# v0_7.net
KiCad netlist of a schematic drawn in EAGLE
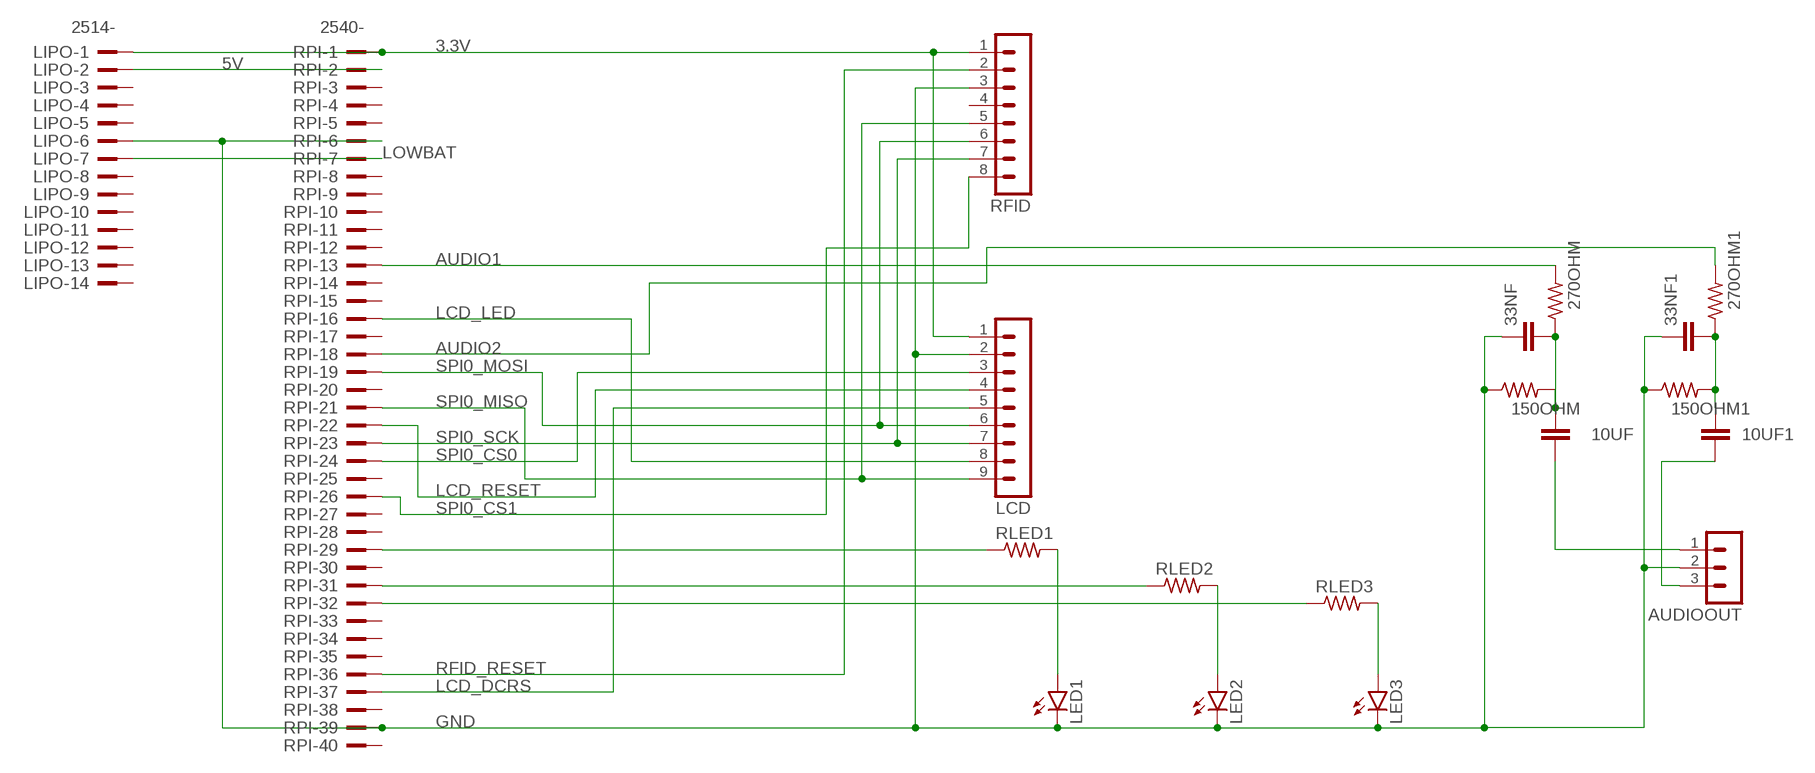
[diagram p0: schematic, sheet 1]

(export (version "E")
  (design (tool "Eeschema 10.0.6"))
  (components
    (comp (ref "10UF")
      (value "C-EU025-025X050")
      (footprint "eagle-import:C025-025X050")
      (libsource (lib "eagle-import") (part "C-EU025-025X050"))
    )
    (comp (ref "10UF1")
      (value "C-EU025-025X050")
      (footprint "eagle-import:C025-025X050")
      (libsource (lib "eagle-import") (part "C-EU025-025X050"))
    )
    (comp (ref "33NF")
      (value "C-EU025-025X050")
      (footprint "eagle-import:C025-025X050")
      (libsource (lib "eagle-import") (part "C-EU025-025X050"))
    )
    (comp (ref "33NF1")
      (value "C-EU025-025X050")
      (footprint "eagle-import:C025-025X050")
      (libsource (lib "eagle-import") (part "C-EU025-025X050"))
    )
    (comp (ref "150OHM")
      (value "R-US_0204/5")
      (footprint "eagle-import:0204_5")
      (libsource (lib "eagle-import") (part "R-US_0204/5"))
    )
    (comp (ref "150OHM1")
      (value "R-US_0204/5")
      (footprint "eagle-import:0204_5")
      (libsource (lib "eagle-import") (part "R-US_0204/5"))
    )
    (comp (ref "270OHM")
      (value "R-US_0204/5")
      (footprint "eagle-import:0204_5")
      (libsource (lib "eagle-import") (part "R-US_0204/5"))
    )
    (comp (ref "270OHM1")
      (value "R-US_0204/5")
      (footprint "eagle-import:0204_5")
      (libsource (lib "eagle-import") (part "R-US_0204/5"))
    )
    (comp (ref "AUDIOOUT")
      (value "MA03-1")
      (footprint "eagle-import:MA03-1")
      (libsource (lib "eagle-import") (part "MA03-1"))
    )
    (comp (ref "LCD")
      (value "MA09-1")
      (footprint "eagle-import:MA09-1")
      (libsource (lib "eagle-import") (part "MA09-1"))
    )
    (comp (ref "LED1")
      (value "LED3MM")
      (footprint "eagle-import:LED3MM")
      (libsource (lib "eagle-import") (part "LED3MM"))
    )
    (comp (ref "LED2")
      (value "LED3MM")
      (footprint "eagle-import:LED3MM")
      (libsource (lib "eagle-import") (part "LED3MM"))
    )
    (comp (ref "LED3")
      (value "LED3MM")
      (footprint "eagle-import:LED3MM")
      (libsource (lib "eagle-import") (part "LED3MM"))
    )
    (comp (ref "LIPO")
      (value "2514-")
      (footprint "eagle-import:PAK100_2500-14")
      (libsource (lib "eagle-import") (part "2514-"))
    )
    (comp (ref "RFID")
      (value "MA08-1")
      (footprint "eagle-import:MA08-1")
      (libsource (lib "eagle-import") (part "MA08-1"))
    )
    (comp (ref "RLED1")
      (value "R-US_0204/5")
      (footprint "eagle-import:0204_5")
      (libsource (lib "eagle-import") (part "R-US_0204/5"))
    )
    (comp (ref "RLED2")
      (value "R-US_0204/5")
      (footprint "eagle-import:0204_5")
      (libsource (lib "eagle-import") (part "R-US_0204/5"))
    )
    (comp (ref "RLED3")
      (value "R-US_0204/5")
      (footprint "eagle-import:0204_5")
      (libsource (lib "eagle-import") (part "R-US_0204/5"))
    )
    (comp (ref "RPI")
      (value "2540-")
      (footprint "eagle-import:PAK100_2500-40")
      (libsource (lib "eagle-import") (part "2540-"))
    )
  )
  (nets
    (net (code "1") (name "/3.3V") (class "Default")
      (node (ref "LCD") (pin "1") (pinfunction "1_1") (pintype "passive"))
      (node (ref "LIPO") (pin "1") (pinfunction "KL_1") (pintype "passive"))
      (node (ref "RFID") (pin "1") (pinfunction "1_1") (pintype "passive"))
      (node (ref "RPI") (pin "1") (pinfunction "KL_1") (pintype "passive"))
    )
    (net (code "2") (name "/5V") (class "Default")
      (node (ref "LIPO") (pin "2") (pinfunction "KL_2") (pintype "passive"))
      (node (ref "RPI") (pin "2") (pinfunction "KL_2") (pintype "passive"))
    )
    (net (code "3") (name "/AUDIO1") (class "Default")
      (node (ref "270OHM") (pin "2") (pinfunction "2_2") (pintype "passive"))
      (node (ref "RPI") (pin "13") (pinfunction "KL_13") (pintype "passive"))
    )
    (net (code "4") (name "/AUDIO2") (class "Default")
      (node (ref "270OHM1") (pin "2") (pinfunction "2_2") (pintype "passive"))
      (node (ref "RPI") (pin "18") (pinfunction "KL_18") (pintype "passive"))
    )
    (net (code "5") (name "/GND") (class "Default")
      (node (ref "150OHM") (pin "1") (pinfunction "1_1") (pintype "passive"))
      (node (ref "150OHM1") (pin "1") (pinfunction "1_1") (pintype "passive"))
      (node (ref "33NF") (pin "1") (pinfunction "1_1") (pintype "passive"))
      (node (ref "33NF1") (pin "1") (pinfunction "1_1") (pintype "passive"))
      (node (ref "AUDIOOUT") (pin "2") (pinfunction "2_2") (pintype "passive"))
      (node (ref "LCD") (pin "2") (pinfunction "2_2") (pintype "passive"))
      (node (ref "LED1") (pin "K") (pinfunction "C_K") (pintype "passive"))
      (node (ref "LED2") (pin "K") (pinfunction "C_K") (pintype "passive"))
      (node (ref "LED3") (pin "K") (pinfunction "C_K") (pintype "passive"))
      (node (ref "LIPO") (pin "6") (pinfunction "KL_6") (pintype "passive"))
      (node (ref "RFID") (pin "3") (pinfunction "3_3") (pintype "passive"))
      (node (ref "RPI") (pin "39") (pinfunction "KL_39") (pintype "passive"))
      (node (ref "RPI") (pin "6") (pinfunction "KL_6") (pintype "passive"))
    )
    (net (code "6") (name "/LCD_DCRS") (class "Default")
      (node (ref "LCD") (pin "5") (pinfunction "5_5") (pintype "passive"))
      (node (ref "RPI") (pin "37") (pinfunction "KL_37") (pintype "passive"))
    )
    (net (code "7") (name "/LCD_LED") (class "Default")
      (node (ref "LCD") (pin "8") (pinfunction "8_8") (pintype "passive"))
      (node (ref "RPI") (pin "16") (pinfunction "KL_16") (pintype "passive"))
    )
    (net (code "8") (name "/LCD_RESET") (class "Default")
      (node (ref "LCD") (pin "4") (pinfunction "4_4") (pintype "passive"))
      (node (ref "RPI") (pin "22") (pinfunction "KL_22") (pintype "passive"))
    )
    (net (code "9") (name "/LOWBAT") (class "Default")
      (node (ref "LIPO") (pin "7") (pinfunction "KL_7") (pintype "passive"))
      (node (ref "RPI") (pin "7") (pinfunction "KL_7") (pintype "passive"))
    )
    (net (code "10") (name "/RFID_RESET") (class "Default")
      (node (ref "RFID") (pin "2") (pinfunction "2_2") (pintype "passive"))
      (node (ref "RPI") (pin "36") (pinfunction "KL_36") (pintype "passive"))
    )
    (net (code "11") (name "/SPI0_CS0") (class "Default")
      (node (ref "LCD") (pin "3") (pinfunction "3_3") (pintype "passive"))
      (node (ref "RPI") (pin "24") (pinfunction "KL_24") (pintype "passive"))
    )
    (net (code "12") (name "/SPI0_CS1") (class "Default")
      (node (ref "RFID") (pin "8") (pinfunction "8_8") (pintype "passive"))
      (node (ref "RPI") (pin "26") (pinfunction "KL_26") (pintype "passive"))
    )
    (net (code "13") (name "/SPI0_MISO") (class "Default")
      (node (ref "LCD") (pin "9") (pinfunction "9_9") (pintype "passive"))
      (node (ref "RFID") (pin "5") (pinfunction "5_5") (pintype "passive"))
      (node (ref "RPI") (pin "21") (pinfunction "KL_21") (pintype "passive"))
    )
    (net (code "14") (name "/SPI0_MOSI") (class "Default")
      (node (ref "LCD") (pin "6") (pinfunction "6_6") (pintype "passive"))
      (node (ref "RFID") (pin "6") (pinfunction "6_6") (pintype "passive"))
      (node (ref "RPI") (pin "19") (pinfunction "KL_19") (pintype "passive"))
    )
    (net (code "15") (name "/SPI0_SCK") (class "Default")
      (node (ref "LCD") (pin "7") (pinfunction "7_7") (pintype "passive"))
      (node (ref "RFID") (pin "7") (pinfunction "7_7") (pintype "passive"))
      (node (ref "RPI") (pin "23") (pinfunction "KL_23") (pintype "passive"))
    )
    (net (code "16") (name "Net-(10UF-Pad1)") (class "Default")
      (node (ref "10UF") (pin "1") (pinfunction "1_1") (pintype "passive"))
      (node (ref "AUDIOOUT") (pin "1") (pinfunction "1_1") (pintype "passive"))
    )
    (net (code "17") (name "Net-(10UF-Pad2)") (class "Default")
      (node (ref "10UF") (pin "2") (pinfunction "2_2") (pintype "passive"))
      (node (ref "150OHM") (pin "2") (pinfunction "2_2") (pintype "passive"))
      (node (ref "270OHM") (pin "1") (pinfunction "1_1") (pintype "passive"))
      (node (ref "33NF") (pin "2") (pinfunction "2_2") (pintype "passive"))
    )
    (net (code "18") (name "Net-(10UF1-Pad1)") (class "Default")
      (node (ref "10UF1") (pin "1") (pinfunction "1_1") (pintype "passive"))
      (node (ref "AUDIOOUT") (pin "3") (pinfunction "3_3") (pintype "passive"))
    )
    (net (code "19") (name "Net-(10UF1-Pad2)") (class "Default")
      (node (ref "10UF1") (pin "2") (pinfunction "2_2") (pintype "passive"))
      (node (ref "150OHM1") (pin "2") (pinfunction "2_2") (pintype "passive"))
      (node (ref "270OHM1") (pin "1") (pinfunction "1_1") (pintype "passive"))
      (node (ref "33NF1") (pin "2") (pinfunction "2_2") (pintype "passive"))
    )
    (net (code "20") (name "Net-(LED1-PadA)") (class "Default")
      (node (ref "LED1") (pin "A") (pinfunction "A_A") (pintype "passive"))
      (node (ref "RLED1") (pin "2") (pinfunction "2_2") (pintype "passive"))
    )
    (net (code "21") (name "Net-(LED2-PadA)") (class "Default")
      (node (ref "LED2") (pin "A") (pinfunction "A_A") (pintype "passive"))
      (node (ref "RLED2") (pin "2") (pinfunction "2_2") (pintype "passive"))
    )
    (net (code "22") (name "Net-(LED3-PadA)") (class "Default")
      (node (ref "LED3") (pin "A") (pinfunction "A_A") (pintype "passive"))
      (node (ref "RLED3") (pin "2") (pinfunction "2_2") (pintype "passive"))
    )
    (net (code "23") (name "Net-(RPIV-KL)") (class "Default")
      (node (ref "RLED1") (pin "1") (pinfunction "1_1") (pintype "passive"))
      (node (ref "RPI") (pin "29") (pinfunction "KL_29") (pintype "passive"))
    )
    (net (code "24") (name "Net-(RPIY-KL)") (class "Default")
      (node (ref "RLED2") (pin "1") (pinfunction "1_1") (pintype "passive"))
      (node (ref "RPI") (pin "31") (pinfunction "KL_31") (pintype "passive"))
    )
    (net (code "25") (name "Net-(RPIZ-KL)") (class "Default")
      (node (ref "RLED3") (pin "1") (pinfunction "1_1") (pintype "passive"))
      (node (ref "RPI") (pin "32") (pinfunction "KL_32") (pintype "passive"))
    )
    (net (code "26") (name "unconnected-(LIPOB-KL-Pad10)") (class "Default")
      (node (ref "LIPO") (pin "10") (pinfunction "KL_10") (pintype "passive"))
    )
    (net (code "27") (name "unconnected-(LIPOC-KL-Pad11)") (class "Default")
      (node (ref "LIPO") (pin "11") (pinfunction "KL_11") (pintype "passive"))
    )
    (net (code "28") (name "unconnected-(LIPOD-KL-Pad12)") (class "Default")
      (node (ref "LIPO") (pin "12") (pinfunction "KL_12") (pintype "passive"))
    )
    (net (code "29") (name "unconnected-(LIPOE-KL-Pad13)") (class "Default")
      (node (ref "LIPO") (pin "13") (pinfunction "KL_13") (pintype "passive"))
    )
    (net (code "30") (name "unconnected-(LIPOF-KL-Pad14)") (class "Default")
      (node (ref "LIPO") (pin "14") (pinfunction "KL_14") (pintype "passive"))
    )
    (net (code "31") (name "unconnected-(LIPOH-KL-Pad3)") (class "Default")
      (node (ref "LIPO") (pin "3") (pinfunction "KL_3") (pintype "passive"))
    )
    (net (code "32") (name "unconnected-(LIPOI-KL-Pad4)") (class "Default")
      (node (ref "LIPO") (pin "4") (pinfunction "KL_4") (pintype "passive"))
    )
    (net (code "33") (name "unconnected-(LIPOJ-KL-Pad5)") (class "Default")
      (node (ref "LIPO") (pin "5") (pinfunction "KL_5") (pintype "passive"))
    )
    (net (code "34") (name "unconnected-(LIPOM-KL-Pad8)") (class "Default")
      (node (ref "LIPO") (pin "8") (pinfunction "KL_8") (pintype "passive"))
    )
    (net (code "35") (name "unconnected-(LIPON-KL-Pad9)") (class "Default")
      (node (ref "LIPO") (pin "9") (pinfunction "KL_9") (pintype "passive"))
    )
    (net (code "36") (name "unconnected-(RFID-Pad4)") (class "Default")
      (node (ref "RFID") (pin "4") (pinfunction "4_4") (pintype "passive"))
    )
    (net (code "37") (name "unconnected-(RPIAA-KL-Pad33)") (class "Default")
      (node (ref "RPI") (pin "33") (pinfunction "KL_33") (pintype "passive"))
    )
    (net (code "38") (name "unconnected-(RPIAB-KL-Pad34)") (class "Default")
      (node (ref "RPI") (pin "34") (pinfunction "KL_34") (pintype "passive"))
    )
    (net (code "39") (name "unconnected-(RPIAC-KL-Pad35)") (class "Default")
      (node (ref "RPI") (pin "35") (pinfunction "KL_35") (pintype "passive"))
    )
    (net (code "40") (name "unconnected-(RPIAF-KL-Pad38)") (class "Default")
      (node (ref "RPI") (pin "38") (pinfunction "KL_38") (pintype "passive"))
    )
    (net (code "41") (name "unconnected-(RPIAH-KL-Pad4)") (class "Default")
      (node (ref "RPI") (pin "4") (pinfunction "KL_4") (pintype "passive"))
    )
    (net (code "42") (name "unconnected-(RPIAI-KL-Pad40)") (class "Default")
      (node (ref "RPI") (pin "40") (pinfunction "KL_40") (pintype "passive"))
    )
    (net (code "43") (name "unconnected-(RPIAJ-KL-Pad5)") (class "Default")
      (node (ref "RPI") (pin "5") (pinfunction "KL_5") (pintype "passive"))
    )
    (net (code "44") (name "unconnected-(RPIAM-KL-Pad8)") (class "Default")
      (node (ref "RPI") (pin "8") (pinfunction "KL_8") (pintype "passive"))
    )
    (net (code "45") (name "unconnected-(RPIAN-KL-Pad9)") (class "Default")
      (node (ref "RPI") (pin "9") (pinfunction "KL_9") (pintype "passive"))
    )
    (net (code "46") (name "unconnected-(RPIB-KL-Pad10)") (class "Default")
      (node (ref "RPI") (pin "10") (pinfunction "KL_10") (pintype "passive"))
    )
    (net (code "47") (name "unconnected-(RPIC-KL-Pad11)") (class "Default")
      (node (ref "RPI") (pin "11") (pinfunction "KL_11") (pintype "passive"))
    )
    (net (code "48") (name "unconnected-(RPID-KL-Pad12)") (class "Default")
      (node (ref "RPI") (pin "12") (pinfunction "KL_12") (pintype "passive"))
    )
    (net (code "49") (name "unconnected-(RPIF-KL-Pad14)") (class "Default")
      (node (ref "RPI") (pin "14") (pinfunction "KL_14") (pintype "passive"))
    )
    (net (code "50") (name "unconnected-(RPIG-KL-Pad15)") (class "Default")
      (node (ref "RPI") (pin "15") (pinfunction "KL_15") (pintype "passive"))
    )
    (net (code "51") (name "unconnected-(RPII-KL-Pad17)") (class "Default")
      (node (ref "RPI") (pin "17") (pinfunction "KL_17") (pintype "passive"))
    )
    (net (code "52") (name "unconnected-(RPIM-KL-Pad20)") (class "Default")
      (node (ref "RPI") (pin "20") (pinfunction "KL_20") (pintype "passive"))
    )
    (net (code "53") (name "unconnected-(RPIR-KL-Pad25)") (class "Default")
      (node (ref "RPI") (pin "25") (pinfunction "KL_25") (pintype "passive"))
    )
    (net (code "54") (name "unconnected-(RPIT-KL-Pad27)") (class "Default")
      (node (ref "RPI") (pin "27") (pinfunction "KL_27") (pintype "passive"))
    )
    (net (code "55") (name "unconnected-(RPIU-KL-Pad28)") (class "Default")
      (node (ref "RPI") (pin "28") (pinfunction "KL_28") (pintype "passive"))
    )
    (net (code "56") (name "unconnected-(RPIW-KL-Pad3)") (class "Default")
      (node (ref "RPI") (pin "3") (pinfunction "KL_3") (pintype "passive"))
    )
    (net (code "57") (name "unconnected-(RPIX-KL-Pad30)") (class "Default")
      (node (ref "RPI") (pin "30") (pinfunction "KL_30") (pintype "passive"))
    )
  )
)
